# RF.net
KiCad netlist of a schematic drawn in Altium Designer
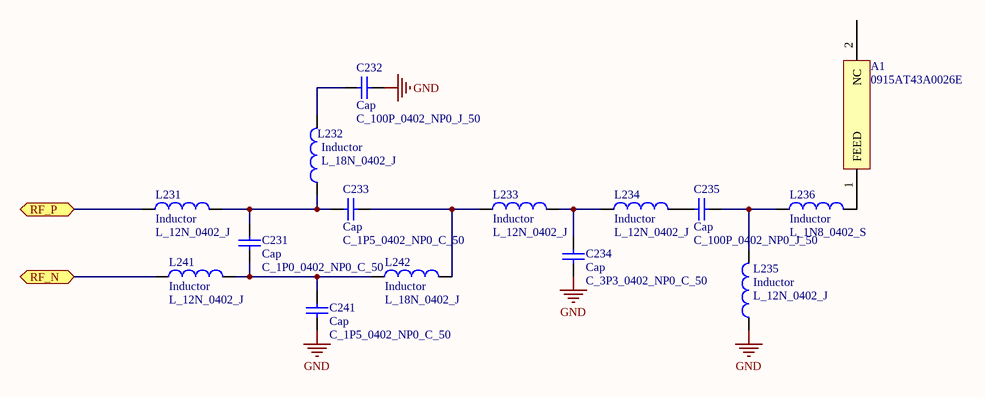
[diagram p0: RF.SchDoc]

(export (version "E")
  (design (tool "Eeschema 10.0.6"))
  (components
    (comp (ref "A1")
      (value "0915AT43A0026E")
      (footprint "0915AT43A0026")
      (description "RF CHIP ANTENNA 902 - 928MHZ")
      (fields (field (name "MANUFACTURER") "Johanson Technology Inc"))
      (libsource (lib "BrewBit") (part "0915AT43A0026E"))
    )
    (comp (ref "C231")
      (value "Cap")
      (footprint "C_0402")
      (description "Capacitor")
      (fields (field (name "ALTIUM_VALUE") "C_1P0_0402_NP0_C_50") (field (name "PUBLISHER") "Altium Limited"))
      (libsource (lib "Miscellaneous Devices") (part "Cap"))
    )
    (comp (ref "C232")
      (value "Cap")
      (footprint "C_0402")
      (description "Capacitor")
      (fields
        (field (name "ALTIUM_VALUE") "C_100P_0402_NP0_J_50")
        (field (name "PUBLISHER") "Altium Limited")
      )
      (libsource (lib "Miscellaneous Devices") (part "Cap"))
    )
    (comp (ref "C233")
      (value "Cap")
      (footprint "C_0402")
      (description "Capacitor")
      (fields (field (name "ALTIUM_VALUE") "C_1P5_0402_NP0_C_50") (field (name "PUBLISHER") "Altium Limited"))
      (libsource (lib "Miscellaneous Devices") (part "Cap"))
    )
    (comp (ref "C234")
      (value "Cap")
      (footprint "C_0402")
      (description "Capacitor")
      (fields (field (name "ALTIUM_VALUE") "C_3P3_0402_NP0_C_50") (field (name "PUBLISHER") "Altium Limited"))
      (libsource (lib "Miscellaneous Devices") (part "Cap"))
    )
    (comp (ref "C235")
      (value "Cap")
      (footprint "C_0402")
      (description "Capacitor")
      (fields
        (field (name "ALTIUM_VALUE") "C_100P_0402_NP0_J_50")
        (field (name "PUBLISHER") "Altium Limited")
      )
      (libsource (lib "Miscellaneous Devices") (part "Cap"))
    )
    (comp (ref "C241")
      (value "Cap")
      (footprint "C_0402")
      (description "Capacitor")
      (fields (field (name "ALTIUM_VALUE") "C_1P5_0402_NP0_C_50") (field (name "PUBLISHER") "Altium Limited"))
      (libsource (lib "Miscellaneous Devices") (part "Cap"))
    )
    (comp (ref "L231")
      (value "Inductor")
      (footprint "R_0402")
      (fields (field (name "ALTIUM_VALUE") "L_12N_0402_J") (field (name "PUBLISHER") "Altium Limited"))
      (libsource (lib "Miscellaneous Devices") (part "Inductor"))
    )
    (comp (ref "L232")
      (value "Inductor")
      (footprint "R_0402")
      (fields (field (name "ALTIUM_VALUE") "L_18N_0402_J") (field (name "PUBLISHER") "Altium Limited"))
      (libsource (lib "Miscellaneous Devices") (part "Inductor"))
    )
    (comp (ref "L233")
      (value "Inductor")
      (footprint "R_0402")
      (fields (field (name "ALTIUM_VALUE") "L_12N_0402_J") (field (name "PUBLISHER") "Altium Limited"))
      (libsource (lib "Miscellaneous Devices") (part "Inductor"))
    )
    (comp (ref "L234")
      (value "Inductor")
      (footprint "R_0402")
      (fields (field (name "ALTIUM_VALUE") "L_12N_0402_J") (field (name "PUBLISHER") "Altium Limited"))
      (libsource (lib "Miscellaneous Devices") (part "Inductor"))
    )
    (comp (ref "L235")
      (value "Inductor")
      (footprint "R_0402")
      (fields (field (name "ALTIUM_VALUE") "L_12N_0402_J") (field (name "PUBLISHER") "Altium Limited"))
      (libsource (lib "Miscellaneous Devices") (part "Inductor"))
    )
    (comp (ref "L236")
      (value "Inductor")
      (footprint "R_0402")
      (fields (field (name "ALTIUM_VALUE") "L_1N8_0402_S") (field (name "PUBLISHER") "Altium Limited"))
      (libsource (lib "Miscellaneous Devices") (part "Inductor"))
    )
    (comp (ref "L241")
      (value "Inductor")
      (fields (field (name "ALTIUM_VALUE") "L_12N_0402_J") (field (name "PUBLISHER") "Altium Limited"))
      (libsource (lib "Miscellaneous Devices") (part "Inductor"))
    )
    (comp (ref "L242")
      (value "Inductor")
      (footprint "R_0402")
      (fields (field (name "ALTIUM_VALUE") "L_18N_0402_J") (field (name "PUBLISHER") "Altium Limited"))
      (libsource (lib "Miscellaneous Devices") (part "Inductor"))
    )
  )
  (nets
    (net (code "1") (name "/RF_N") (class "Default")
      (node (ref "L241") (pin "1") (pinfunction "1_1") (pintype "passive"))
    )
    (net (code "2") (name "/RF_P") (class "Default")
      (node (ref "L231") (pin "1") (pinfunction "1_1") (pintype "passive"))
    )
    (net (code "3") (name "GND") (class "Default")
      (node (ref "C232") (pin "2") (pinfunction "2_2") (pintype "passive"))
      (node (ref "C234") (pin "1") (pinfunction "1_1") (pintype "passive"))
      (node (ref "C241") (pin "1") (pinfunction "1_1") (pintype "passive"))
      (node (ref "L235") (pin "1") (pinfunction "1_1") (pintype "passive"))
    )
    (net (code "4") (name "Net-(A1-FEED)") (class "Default")
      (node (ref "A1") (pin "1") (pinfunction "FEED_1") (pintype "passive"))
      (node (ref "L236") (pin "2") (pinfunction "2_2") (pintype "passive"))
    )
    (net (code "5") (name "Net-(C231-Pad1)") (class "Default")
      (node (ref "C231") (pin "1") (pinfunction "1_1") (pintype "passive"))
      (node (ref "C241") (pin "2") (pinfunction "2_2") (pintype "passive"))
      (node (ref "L241") (pin "2") (pinfunction "2_2") (pintype "passive"))
      (node (ref "L242") (pin "1") (pinfunction "1_1") (pintype "passive"))
    )
    (net (code "6") (name "Net-(C231-Pad2)") (class "Default")
      (node (ref "C231") (pin "2") (pinfunction "2_2") (pintype "passive"))
      (node (ref "C233") (pin "1") (pinfunction "1_1") (pintype "passive"))
      (node (ref "L231") (pin "2") (pinfunction "2_2") (pintype "passive"))
      (node (ref "L232") (pin "1") (pinfunction "1_1") (pintype "passive"))
    )
    (net (code "7") (name "Net-(C232-Pad1)") (class "Default")
      (node (ref "C232") (pin "1") (pinfunction "1_1") (pintype "passive"))
      (node (ref "L232") (pin "2") (pinfunction "2_2") (pintype "passive"))
    )
    (net (code "8") (name "Net-(C233-Pad2)") (class "Default")
      (node (ref "C233") (pin "2") (pinfunction "2_2") (pintype "passive"))
      (node (ref "L233") (pin "1") (pinfunction "1_1") (pintype "passive"))
      (node (ref "L242") (pin "2") (pinfunction "2_2") (pintype "passive"))
    )
    (net (code "9") (name "Net-(C234-Pad2)") (class "Default")
      (node (ref "C234") (pin "2") (pinfunction "2_2") (pintype "passive"))
      (node (ref "L233") (pin "2") (pinfunction "2_2") (pintype "passive"))
      (node (ref "L234") (pin "1") (pinfunction "1_1") (pintype "passive"))
    )
    (net (code "10") (name "Net-(C235-Pad1)") (class "Default")
      (node (ref "C235") (pin "1") (pinfunction "1_1") (pintype "passive"))
      (node (ref "L234") (pin "2") (pinfunction "2_2") (pintype "passive"))
    )
    (net (code "11") (name "Net-(C235-Pad2)") (class "Default")
      (node (ref "C235") (pin "2") (pinfunction "2_2") (pintype "passive"))
      (node (ref "L235") (pin "2") (pinfunction "2_2") (pintype "passive"))
      (node (ref "L236") (pin "1") (pinfunction "1_1") (pintype "passive"))
    )
    (net (code "12") (name "unconnected-(A1-NC-Pad2)") (class "Default")
      (node (ref "A1") (pin "2") (pinfunction "NC_2") (pintype "passive"))
    )
  )
)
